# Ethernet.net
KiCad netlist of a schematic drawn in Altium Designer
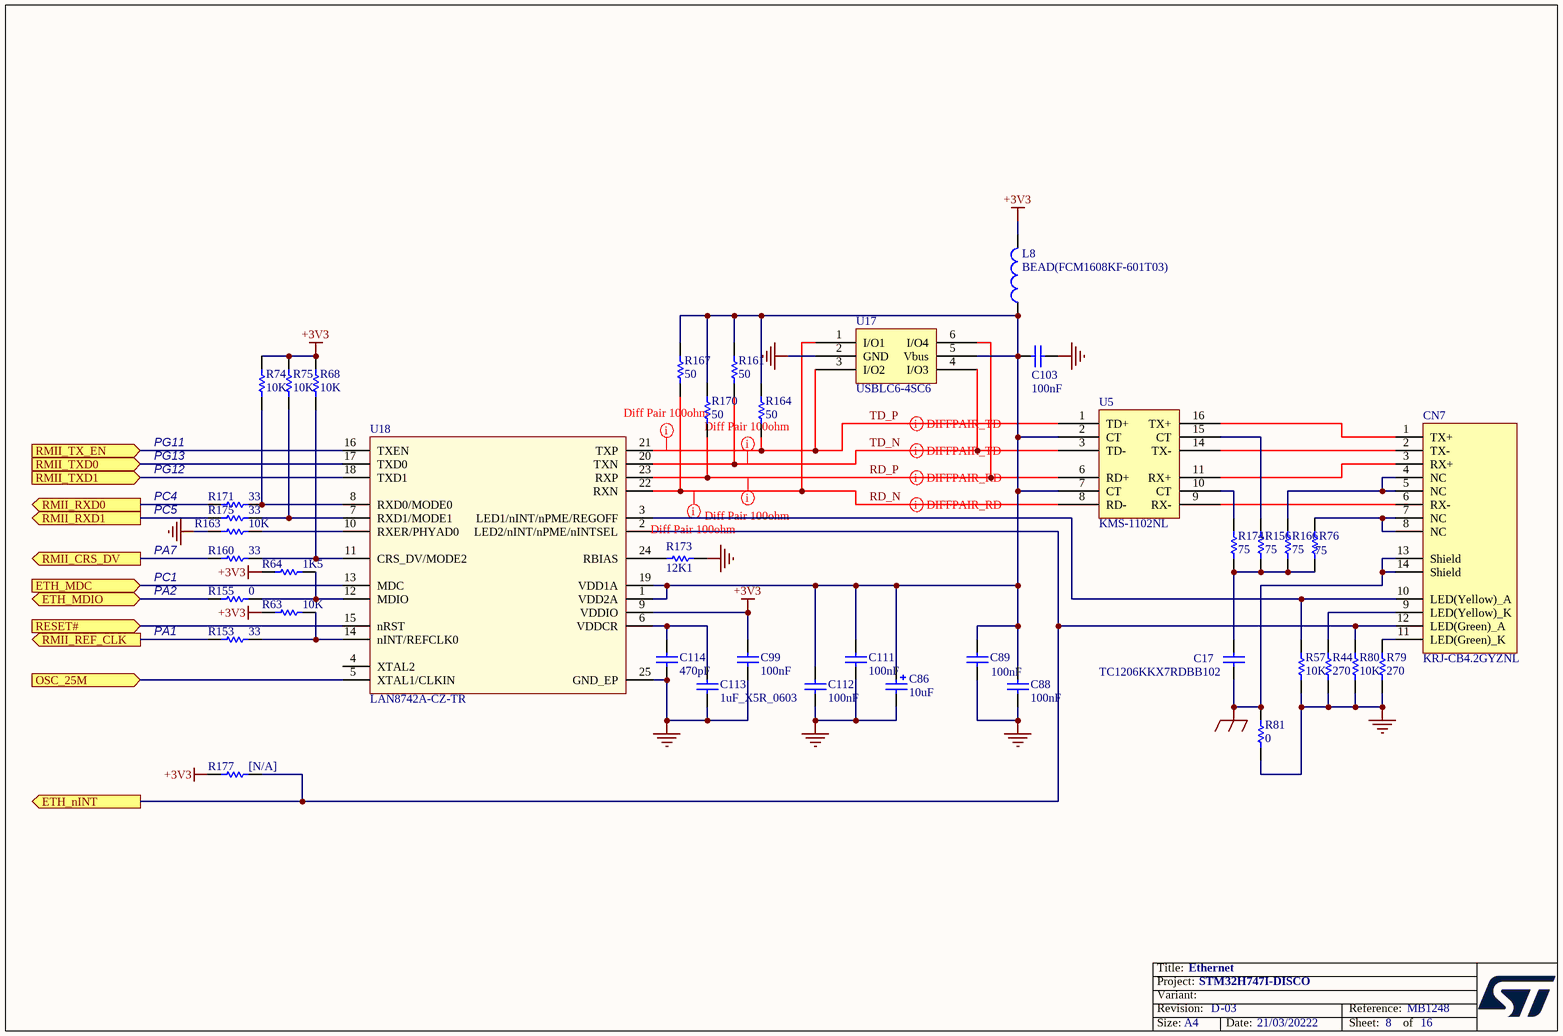
[diagram p0: Ethernet.SchDoc]

(export (version "E")
  (design (tool "Eeschema 10.0.6"))
  (components
    (comp (ref "C17")
      (value "TC1206KKX7RDBB102")
      (footprint "1206C")
      (description "Capacitor 0402 / 0603 / 0805/ 1206")
      (libsource (lib "MCD_TOOLS") (part "Capacitor_ST"))
    )
    (comp (ref "C86")
      (value "10uF")
      (footprint "TAN-A")
      (description "Polarized Capacitor,10uF,10V,10%,typeA,VISHAY")
      (libsource (lib "MCD_TOOLS") (part "Cap_10uF_POL_10%_TANA"))
    )
    (comp (ref "C88")
      (value "100nF")
      (footprint "0603C")
      (description "Capacitor 0402 / 0603 / 0805")
      (libsource (lib "MCD_TOOLS") (part "Capacitor_ST"))
    )
    (comp (ref "C89")
      (value "100nF")
      (footprint "0603C")
      (description "Capacitor 0402 / 0603 / 0805")
      (libsource (lib "MCD_TOOLS") (part "Capacitor_ST"))
    )
    (comp (ref "C99")
      (value "100nF")
      (footprint "0603C")
      (description "Capacitor 0402 / 0603 / 0805")
      (libsource (lib "MCD_TOOLS") (part "Capacitor_ST"))
    )
    (comp (ref "C103")
      (value "100nF")
      (footprint "0603C")
      (description "Capacitor 0402 / 0603 / 0805")
      (libsource (lib "MCD_TOOLS") (part "Capacitor_ST"))
    )
    (comp (ref "C111")
      (value "100nF")
      (footprint "0603C")
      (description "Capacitor 0402 / 0603 / 0805")
      (libsource (lib "MCD_TOOLS") (part "Capacitor_ST"))
    )
    (comp (ref "C112")
      (value "100nF")
      (footprint "0603C")
      (description "Capacitor 0402 / 0603 / 0805")
      (libsource (lib "MCD_TOOLS") (part "Capacitor_ST"))
    )
    (comp (ref "C113")
      (value "1uF_X5R_0603")
      (footprint "0603C")
      (description "0603  X5R 1礔")
      (fields (field (name "TOLERANCE") "10%"))
      (libsource (lib "MB963_1") (part "CAP SMD 0603  X5R 1礔 25V 10%"))
    )
    (comp (ref "C114")
      (value "470pF")
      (footprint "0603C")
      (description "Capacitor 0402 / 0603 / 0805")
      (libsource (lib "MCD_TOOLS") (part "Capacitor_ST"))
    )
    (comp (ref "CN7")
      (value "KRJ-CB4.2GYZNL")
      (footprint "RJ45_LED_KRJ-CB4R2GYZNL_EM")
      (description "100 Base-TX (Fast Ethernet) SMD RJ45 single port (1x1) with LEDS Integrated Magnetics Connector")
      (libsource (lib "MB1137") (part "KRJ-CB4.2GYZNL"))
    )
    (comp (ref "L8")
      (value "BEAD(FCM1608KF-601T03)")
      (footprint "0603L")
      (description "Inductor")
      (fields (field (name "PUBLISHER") "Altium Limited"))
      (libsource (lib "Miscellaneous Devices") (part "Inductor"))
    )
    (comp (ref "R44")
      (value "270")
      (footprint "0603R")
      (description "Resistor 0402 / 0603 / 0805")
      (libsource (lib "Miscellaneous Devices") (part "Res1"))
    )
    (comp (ref "R57")
      (value "10K")
      (footprint "0603R")
      (description "Resistor 0402 / 0603 / 0805")
      (libsource (lib "Miscellaneous Devices") (part "Res1"))
    )
    (comp (ref "R63")
      (value "10K")
      (footprint "0603R")
      (description "Resistor 0402 / 0603 / 0805")
      (libsource (lib "Miscellaneous Devices") (part "Res1"))
    )
    (comp (ref "R64")
      (value "1K5")
      (footprint "0603R")
      (description "Resistor,1K5,0402,1%,YAGEO")
      (libsource (lib "MCD_TOOLS") (part "Res_1K5_1%_0402"))
    )
    (comp (ref "R68")
      (value "10K")
      (footprint "0603R")
      (description "Resistor 0402 / 0603 / 0805")
      (libsource (lib "Miscellaneous Devices") (part "Res1"))
    )
    (comp (ref "R74")
      (value "10K")
      (footprint "0603R")
      (description "Resistor 0402 / 0603 / 0805")
      (libsource (lib "Miscellaneous Devices") (part "Res1"))
    )
    (comp (ref "R75")
      (value "10K")
      (footprint "0603R")
      (description "Resistor 0402 / 0603 / 0805")
      (libsource (lib "Miscellaneous Devices") (part "Res1"))
    )
    (comp (ref "R76")
      (value "75")
      (footprint "0603R")
      (description "Resistor,75,0603,1%,YAGEO")
      (libsource (lib "MB1137") (part "Res_75_1%_0603"))
    )
    (comp (ref "R79")
      (value "270")
      (footprint "0603R")
      (description "Resistor 0402 / 0603 / 0805")
      (libsource (lib "Miscellaneous Devices") (part "Res1"))
    )
    (comp (ref "R80")
      (value "10K")
      (footprint "0603R")
      (description "Resistor 0402 / 0603 / 0805")
      (libsource (lib "Miscellaneous Devices") (part "Res1"))
    )
    (comp (ref "R81")
      (value "0")
      (footprint "0805R")
      (description "Resistor,75,0603,1%,YAGEO")
      (libsource (lib "MB1137") (part "Res_75_1%_0603"))
    )
    (comp (ref "R153")
      (value "33")
      (footprint "0603R")
      (description "Resistor,33,0402,1%,YAGEO")
      (libsource (lib "MCD_TOOLS") (part "Res_33_1%_0402"))
    )
    (comp (ref "R155")
      (value "0")
      (footprint "0603R")
      (description "Resistor")
      (fields (field (name "PUBLISHER") "Altium Limited"))
      (libsource (lib "") (part "Res1_1"))
    )
    (comp (ref "R156")
      (value "75")
      (footprint "0603R")
      (description "Resistor,75,0603,1%,YAGEO")
      (libsource (lib "MB1137") (part "Res_75_1%_0603"))
    )
    (comp (ref "R160")
      (value "33")
      (footprint "0603R")
      (description "Resistor,33,0402,1%,YAGEO")
      (libsource (lib "MCD_TOOLS") (part "Res_33_1%_0402"))
    )
    (comp (ref "R161")
      (value "50")
      (footprint "0603R")
      (description "Resistor,50,0603,1%,YAGEO")
      (libsource (lib "MB1137") (part "Res_50_1%_0603"))
    )
    (comp (ref "R163")
      (value "10K")
      (footprint "0603R")
      (description "Resistor 0402 / 0603 / 0805")
      (libsource (lib "Miscellaneous Devices") (part "Res1"))
    )
    (comp (ref "R164")
      (value "50")
      (footprint "0603R")
      (description "Resistor,50,0603,1%,YAGEO")
      (libsource (lib "MB1137") (part "Res_50_1%_0603"))
    )
    (comp (ref "R166")
      (value "75")
      (footprint "0603R")
      (description "Resistor,75,0603,1%,YAGEO")
      (libsource (lib "MB1137") (part "Res_75_1%_0603"))
    )
    (comp (ref "R167")
      (value "50")
      (footprint "0603R")
      (description "Resistor,50,0603,1%,YAGEO")
      (libsource (lib "MB1137") (part "Res_50_1%_0603"))
    )
    (comp (ref "R170")
      (value "50")
      (footprint "0603R")
      (description "Resistor,50,0603,1%,YAGEO")
      (libsource (lib "MB1137") (part "Res_50_1%_0603"))
    )
    (comp (ref "R171")
      (value "33")
      (footprint "0603R")
      (description "Resistor,33,0402,1%,YAGEO")
      (libsource (lib "MCD_TOOLS") (part "Res_33_1%_0402"))
    )
    (comp (ref "R173")
      (value "12K1")
      (footprint "0603R")
      (description "Resistor,12K1,0603,1%,VISHAY")
      (libsource (lib "MCD_TOOLS") (part "Res_12K1_1%_0603"))
    )
    (comp (ref "R174")
      (value "75")
      (footprint "0603R")
      (description "Resistor,75,0603,1%,YAGEO")
      (libsource (lib "MB1137") (part "Res_75_1%_0603"))
    )
    (comp (ref "R175")
      (value "33")
      (footprint "0603R")
      (description "Resistor,33,0402,1%,YAGEO")
      (libsource (lib "MCD_TOOLS") (part "Res_33_1%_0402"))
    )
    (comp (ref "R177")
      (value "[N/A]")
      (footprint "0603R")
      (description "Resistor")
      (fields (field (name "PUBLISHER") "Altium Limited"))
      (libsource (lib "Miscellaneous Devices") (part "res1"))
    )
    (comp (ref "U5")
      (value "KMS-1102NL")
      (footprint "TF_16SM_12R7X9R65")
      (libsource (lib "MB1248_1") (part "KMS-1102NL"))
    )
    (comp (ref "U17")
      (value "USBLC6-4SC6")
      (footprint "SOT23-6")
      (libsource (lib "MB1248_1") (part "USBLC6-4SC6"))
    )
    (comp (ref "U18")
      (value "LAN8742A-CZ-TR")
      (footprint "QFN24_0R5_4X4")
      (libsource (lib "MB1137") (part "LAN8742A-CZ-TR"))
    )
  )
  (nets
    (net (code "1") (name "+3V3") (class "Default")
      (node (ref "C99") (pin "2") (pinfunction "2_2") (pintype "passive"))
      (node (ref "L8") (pin "2") (pinfunction "2_2") (pintype "passive"))
      (node (ref "R177") (pin "1") (pinfunction "1_1") (pintype "passive"))
      (node (ref "R63") (pin "1") (pinfunction "1_1") (pintype "passive"))
      (node (ref "R64") (pin "2") (pinfunction "2_2") (pintype "passive"))
      (node (ref "R68") (pin "1") (pinfunction "1_1") (pintype "passive"))
      (node (ref "R74") (pin "1") (pinfunction "1_1") (pintype "passive"))
      (node (ref "R75") (pin "1") (pinfunction "1_1") (pintype "passive"))
      (node (ref "U18") (pin "9") (pinfunction "VDDIO_9") (pintype "passive"))
    )
    (net (code "2") (name "/ETH_MDC") (class "Default")
      (node (ref "U18") (pin "13") (pinfunction "MDC_13") (pintype "passive"))
    )
    (net (code "3") (name "/ETH_MDIO") (class "Default")
      (node (ref "R155") (pin "2") (pinfunction "2_2") (pintype "passive"))
    )
    (net (code "4") (name "/ETH_nINT") (class "Default")
      (node (ref "CN7") (pin "12") (pinfunction "LED(Green)_A_12") (pintype "passive"))
      (node (ref "R177") (pin "2") (pinfunction "2_2") (pintype "passive"))
      (node (ref "R80") (pin "1") (pinfunction "1_1") (pintype "passive"))
      (node (ref "U18") (pin "2") (pinfunction "LED2/nINT/nPME/nINTSEL_2") (pintype "passive"))
    )
    (net (code "5") (name "/OSC_25M") (class "Default")
      (node (ref "U18") (pin "5") (pinfunction "XTAL1/CLKIN_5") (pintype "passive"))
    )
    (net (code "6") (name "/RD_N") (class "Default")
      (node (ref "R167") (pin "1") (pinfunction "1_1") (pintype "passive"))
      (node (ref "U17") (pin "1") (pinfunction "I/O1_1") (pintype "passive"))
      (node (ref "U18") (pin "22") (pinfunction "RXN_22") (pintype "passive"))
      (node (ref "U5") (pin "8") (pinfunction "RD-_8") (pintype "passive"))
    )
    (net (code "7") (name "/RD_P") (class "Default")
      (node (ref "R170") (pin "1") (pinfunction "1_1") (pintype "passive"))
      (node (ref "U17") (pin "6") (pinfunction "I/O4_6") (pintype "passive"))
      (node (ref "U18") (pin "23") (pinfunction "RXP_23") (pintype "passive"))
      (node (ref "U5") (pin "6") (pinfunction "RD+_6") (pintype "passive"))
    )
    (net (code "8") (name "/RESET#") (class "Default")
      (node (ref "U18") (pin "15") (pinfunction "nRST_15") (pintype "passive"))
    )
    (net (code "9") (name "/RMII_CRS_DV") (class "Default")
      (node (ref "R160") (pin "2") (pinfunction "2_2") (pintype "passive"))
    )
    (net (code "10") (name "/RMII_REF_CLK") (class "Default")
      (node (ref "R153") (pin "2") (pinfunction "2_2") (pintype "passive"))
    )
    (net (code "11") (name "/RMII_RXD0") (class "Default")
      (node (ref "R171") (pin "2") (pinfunction "2_2") (pintype "passive"))
    )
    (net (code "12") (name "/RMII_RXD1") (class "Default")
      (node (ref "R175") (pin "2") (pinfunction "2_2") (pintype "passive"))
    )
    (net (code "13") (name "/RMII_TXD0") (class "Default")
      (node (ref "U18") (pin "17") (pinfunction "TXD0_17") (pintype "passive"))
    )
    (net (code "14") (name "/RMII_TXD1") (class "Default")
      (node (ref "U18") (pin "18") (pinfunction "TXD1_18") (pintype "passive"))
    )
    (net (code "15") (name "/RMII_TX_EN") (class "Default")
      (node (ref "U18") (pin "16") (pinfunction "TXEN_16") (pintype "passive"))
    )
    (net (code "16") (name "/TD_N") (class "Default")
      (node (ref "R161") (pin "1") (pinfunction "1_1") (pintype "passive"))
      (node (ref "U17") (pin "4") (pinfunction "I/O3_4") (pintype "passive"))
      (node (ref "U18") (pin "20") (pinfunction "TXN_20") (pintype "passive"))
      (node (ref "U5") (pin "3") (pinfunction "TD-_3") (pintype "passive"))
    )
    (net (code "17") (name "/TD_P") (class "Default")
      (node (ref "R164") (pin "1") (pinfunction "1_1") (pintype "passive"))
      (node (ref "U17") (pin "3") (pinfunction "I/O2_3") (pintype "passive"))
      (node (ref "U18") (pin "21") (pinfunction "TXP_21") (pintype "passive"))
      (node (ref "U5") (pin "1") (pinfunction "TD+_1") (pintype "passive"))
    )
    (net (code "18") (name "EGND") (class "Default")
      (node (ref "C17") (pin "1") (pinfunction "1_1") (pintype "passive"))
      (node (ref "CN7") (pin "13") (pinfunction "Shield_13") (pintype "passive"))
      (node (ref "CN7") (pin "14") (pinfunction "Shield_14") (pintype "passive"))
      (node (ref "R81") (pin "1") (pinfunction "1_1") (pintype "passive"))
    )
    (net (code "19") (name "GND") (class "Default")
      (node (ref "C103") (pin "1") (pinfunction "1_1") (pintype "passive"))
      (node (ref "C111") (pin "1") (pinfunction "1_1") (pintype "passive"))
      (node (ref "C112") (pin "1") (pinfunction "1_1") (pintype "passive"))
      (node (ref "C113") (pin "2") (pinfunction "2_2") (pintype "passive"))
      (node (ref "C114") (pin "1") (pinfunction "1_1") (pintype "passive"))
      (node (ref "C86") (pin "2") (pinfunction "2_2") (pintype "passive"))
      (node (ref "C88") (pin "1") (pinfunction "1_1") (pintype "passive"))
      (node (ref "C89") (pin "1") (pinfunction "1_1") (pintype "passive"))
      (node (ref "C99") (pin "1") (pinfunction "1_1") (pintype "passive"))
      (node (ref "R163") (pin "2") (pinfunction "2_2") (pintype "passive"))
      (node (ref "R173") (pin "2") (pinfunction "2_2") (pintype "passive"))
      (node (ref "R44") (pin "2") (pinfunction "2_2") (pintype "passive"))
      (node (ref "R57") (pin "2") (pinfunction "2_2") (pintype "passive"))
      (node (ref "R79") (pin "2") (pinfunction "2_2") (pintype "passive"))
      (node (ref "R80") (pin "2") (pinfunction "2_2") (pintype "passive"))
      (node (ref "R81") (pin "2") (pinfunction "2_2") (pintype "passive"))
      (node (ref "U17") (pin "2") (pinfunction "GND_2") (pintype "passive"))
      (node (ref "U18") (pin "25") (pinfunction "GND_EP_25") (pintype "passive"))
    )
    (net (code "20") (name "Net-(C17-Pad2)") (class "Default")
      (node (ref "C17") (pin "2") (pinfunction "2_2") (pintype "passive"))
      (node (ref "R156") (pin "1") (pinfunction "1_1") (pintype "passive"))
      (node (ref "R166") (pin "1") (pinfunction "1_1") (pintype "passive"))
      (node (ref "R174") (pin "1") (pinfunction "1_1") (pintype "passive"))
      (node (ref "R76") (pin "1") (pinfunction "1_1") (pintype "passive"))
    )
    (net (code "21") (name "Net-(CN7-LED(Green)_K)") (class "Default")
      (node (ref "CN7") (pin "11") (pinfunction "LED(Green)_K_11") (pintype "passive"))
      (node (ref "R79") (pin "1") (pinfunction "1_1") (pintype "passive"))
    )
    (net (code "22") (name "Net-(CN7-LED(Yellow)_A)") (class "Default")
      (node (ref "CN7") (pin "10") (pinfunction "LED(Yellow)_A_10") (pintype "passive"))
      (node (ref "R57") (pin "1") (pinfunction "1_1") (pintype "passive"))
      (node (ref "U18") (pin "3") (pinfunction "LED1/nINT/nPME/REGOFF_3") (pintype "passive"))
    )
    (net (code "23") (name "Net-(CN7-LED(Yellow)_K)") (class "Default")
      (node (ref "CN7") (pin "9") (pinfunction "LED(Yellow)_K_9") (pintype "passive"))
      (node (ref "R44") (pin "1") (pinfunction "1_1") (pintype "passive"))
    )
    (net (code "24") (name "Net-(CN7-NC-Pad4)") (class "Default")
      (node (ref "CN7") (pin "4") (pinfunction "NC_4") (pintype "passive"))
      (node (ref "CN7") (pin "5") (pinfunction "NC_5") (pintype "passive"))
      (node (ref "R166") (pin "2") (pinfunction "2_2") (pintype "passive"))
    )
    (net (code "25") (name "Net-(CN7-NC-Pad7)") (class "Default")
      (node (ref "CN7") (pin "7") (pinfunction "NC_7") (pintype "passive"))
      (node (ref "CN7") (pin "8") (pinfunction "NC_8") (pintype "passive"))
      (node (ref "R76") (pin "2") (pinfunction "2_2") (pintype "passive"))
    )
    (net (code "26") (name "Net-(CN7-RX+)") (class "Default")
      (node (ref "CN7") (pin "3") (pinfunction "RX+_3") (pintype "passive"))
      (node (ref "U5") (pin "11") (pinfunction "RX+_11") (pintype "passive"))
    )
    (net (code "27") (name "Net-(CN7-RX-)") (class "Default")
      (node (ref "CN7") (pin "6") (pinfunction "RX-_6") (pintype "passive"))
      (node (ref "U5") (pin "9") (pinfunction "RX-_9") (pintype "passive"))
    )
    (net (code "28") (name "Net-(CN7-TX+)") (class "Default")
      (node (ref "CN7") (pin "1") (pinfunction "TX+_1") (pintype "passive"))
      (node (ref "U5") (pin "16") (pinfunction "TX+_16") (pintype "passive"))
    )
    (net (code "29") (name "Net-(CN7-TX-)") (class "Default")
      (node (ref "CN7") (pin "2") (pinfunction "TX-_2") (pintype "passive"))
      (node (ref "U5") (pin "14") (pinfunction "TX-_14") (pintype "passive"))
    )
    (net (code "30") (name "Net-(R156-Pad2)") (class "Default")
      (node (ref "R156") (pin "2") (pinfunction "2_2") (pintype "passive"))
      (node (ref "U5") (pin "15") (pinfunction "CT_15") (pintype "passive"))
    )
    (net (code "31") (name "Net-(R174-Pad2)") (class "Default")
      (node (ref "R174") (pin "2") (pinfunction "2_2") (pintype "passive"))
      (node (ref "U5") (pin "10") (pinfunction "CT_10") (pintype "passive"))
    )
    (net (code "32") (name "Net-(U17-Vbus)") (class "Default")
      (node (ref "C103") (pin "2") (pinfunction "2_2") (pintype "passive"))
      (node (ref "C111") (pin "2") (pinfunction "2_2") (pintype "passive"))
      (node (ref "C112") (pin "2") (pinfunction "2_2") (pintype "passive"))
      (node (ref "C86") (pin "1") (pinfunction "1_1") (pintype "passive"))
      (node (ref "C88") (pin "2") (pinfunction "2_2") (pintype "passive"))
      (node (ref "C89") (pin "2") (pinfunction "2_2") (pintype "passive"))
      (node (ref "L8") (pin "1") (pinfunction "1_1") (pintype "passive"))
      (node (ref "R161") (pin "2") (pinfunction "2_2") (pintype "passive"))
      (node (ref "R164") (pin "2") (pinfunction "2_2") (pintype "passive"))
      (node (ref "R167") (pin "2") (pinfunction "2_2") (pintype "passive"))
      (node (ref "R170") (pin "2") (pinfunction "2_2") (pintype "passive"))
      (node (ref "U17") (pin "5") (pinfunction "Vbus_5") (pintype "passive"))
      (node (ref "U18") (pin "1") (pinfunction "VDD2A_1") (pintype "passive"))
      (node (ref "U18") (pin "19") (pinfunction "VDD1A_19") (pintype "passive"))
      (node (ref "U5") (pin "2") (pinfunction "CT_2") (pintype "passive"))
      (node (ref "U5") (pin "7") (pinfunction "CT_7") (pintype "passive"))
    )
    (net (code "33") (name "Net-(U18-CRS_DV{slash}MODE2)") (class "Default")
      (node (ref "R160") (pin "1") (pinfunction "1_1") (pintype "passive"))
      (node (ref "R68") (pin "2") (pinfunction "2_2") (pintype "passive"))
      (node (ref "U18") (pin "11") (pinfunction "CRS_DV/MODE2_11") (pintype "passive"))
    )
    (net (code "34") (name "Net-(U18-MDIO)") (class "Default")
      (node (ref "R155") (pin "1") (pinfunction "1_1") (pintype "passive"))
      (node (ref "R64") (pin "1") (pinfunction "1_1") (pintype "passive"))
      (node (ref "U18") (pin "12") (pinfunction "MDIO_12") (pintype "passive"))
    )
    (net (code "35") (name "Net-(U18-RBIAS)") (class "Default")
      (node (ref "R173") (pin "1") (pinfunction "1_1") (pintype "passive"))
      (node (ref "U18") (pin "24") (pinfunction "RBIAS_24") (pintype "passive"))
    )
    (net (code "36") (name "Net-(U18-RXD0{slash}MODE0)") (class "Default")
      (node (ref "R171") (pin "1") (pinfunction "1_1") (pintype "passive"))
      (node (ref "R74") (pin "2") (pinfunction "2_2") (pintype "passive"))
      (node (ref "U18") (pin "8") (pinfunction "RXD0/MODE0_8") (pintype "passive"))
    )
    (net (code "37") (name "Net-(U18-RXD1{slash}MODE1)") (class "Default")
      (node (ref "R175") (pin "1") (pinfunction "1_1") (pintype "passive"))
      (node (ref "R75") (pin "2") (pinfunction "2_2") (pintype "passive"))
      (node (ref "U18") (pin "7") (pinfunction "RXD1/MODE1_7") (pintype "passive"))
    )
    (net (code "38") (name "Net-(U18-RXER{slash}PHYAD0)") (class "Default")
      (node (ref "R163") (pin "1") (pinfunction "1_1") (pintype "passive"))
      (node (ref "U18") (pin "10") (pinfunction "RXER/PHYAD0_10") (pintype "passive"))
    )
    (net (code "39") (name "Net-(U18-VDDCR)") (class "Default")
      (node (ref "C113") (pin "1") (pinfunction "1_1") (pintype "passive"))
      (node (ref "C114") (pin "2") (pinfunction "2_2") (pintype "passive"))
      (node (ref "U18") (pin "6") (pinfunction "VDDCR_6") (pintype "passive"))
    )
    (net (code "40") (name "Net-(U18-nINT{slash}REFCLK0)") (class "Default")
      (node (ref "R153") (pin "1") (pinfunction "1_1") (pintype "passive"))
      (node (ref "R63") (pin "2") (pinfunction "2_2") (pintype "passive"))
      (node (ref "U18") (pin "14") (pinfunction "nINT/REFCLK0_14") (pintype "passive"))
    )
    (net (code "41") (name "unconnected-(U18-XTAL2-Pad4)") (class "Default")
      (node (ref "U18") (pin "4") (pinfunction "XTAL2_4") (pintype "passive"))
    )
  )
)
